# H2_Sensor.net
KiCad netlist of a schematic drawn in Altium Designer
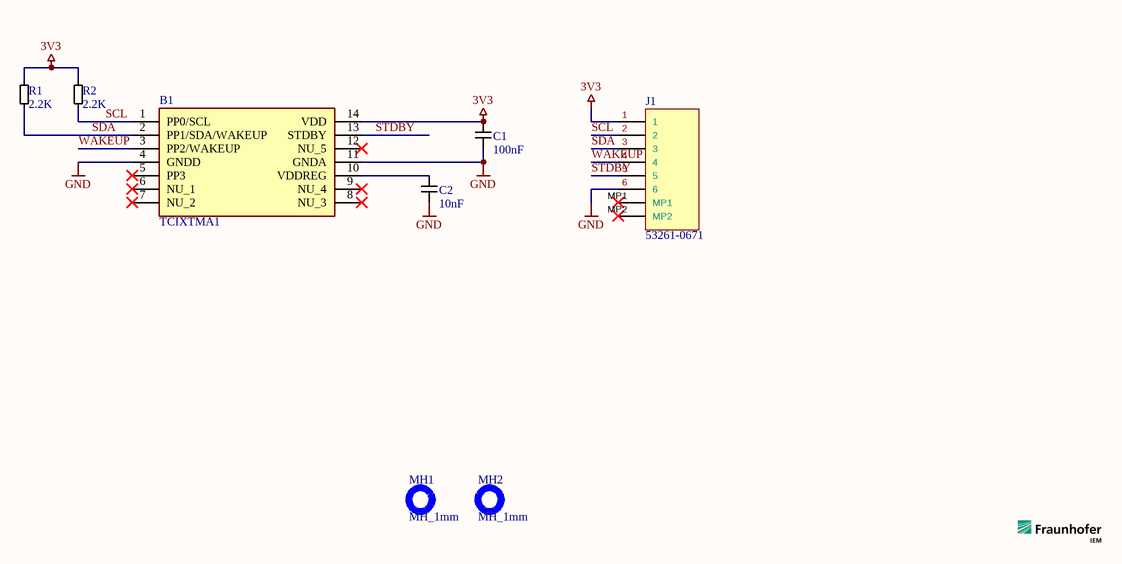
[diagram p0: H2 Sensor.SchDoc]

(export (version "E")
  (design (tool "Eeschema 10.0.6"))
  (components
    (comp (ref "B1")
      (value "TCIXTMA1")
      (footprint "SOP65P890X370-14N")
      (libsource (lib "Schlib1_Farhan") (part "TCIXTMA1"))
    )
    (comp (ref "C1")
      (value "100nF")
      (footprint "Capacitor 0402_1005Metric SMD")
      (description "Capacitor 0402_1005Metric SMD")
      (libsource (lib "Schlib1_Farhan") (part "Capacitor 0402_1005Metric SMD"))
    )
    (comp (ref "C2")
      (value "10nF")
      (footprint "Capacitor 0402_1005Metric SMD")
      (description "Capacitor 0402_1005Metric SMD")
      (libsource (lib "Schlib1_Farhan") (part "Capacitor 0402_1005Metric SMD"))
    )
    (comp (ref "J1")
      (value "53261-0671")
      (footprint "53261-0671")
      (description "PicoBlade 1x6 Horizontal \r\nPCB Header 1.25mm Pitch")
      (libsource (lib "Schlib1_Farhan") (part "53261-0671"))
    )
    (comp (ref "MH1")
      (value "MH_1mm")
      (footprint "MountingHole_1mm_M1")
      (libsource (lib "Schlib1_Farhan") (part "MountingHole_1mm_M1"))
    )
    (comp (ref "MH2")
      (value "MH_1mm")
      (footprint "MountingHole_1mm_M1")
      (libsource (lib "Schlib1_Farhan") (part "MountingHole_1mm_M1"))
    )
    (comp (ref "R1")
      (value "2.2K")
      (footprint "Resistor 0402_1005Metric SMD")
      (description "Resistor 0402_1005Metric SMD")
      (libsource (lib "Schlib1_Farhan") (part "Resistor 0402_1005Metric SMD"))
    )
    (comp (ref "R2")
      (value "2.2K")
      (footprint "Resistor 0402_1005Metric SMD")
      (description "Resistor 0402_1005Metric SMD")
      (libsource (lib "Schlib1_Farhan") (part "Resistor 0402_1005Metric SMD"))
    )
  )
  (nets
    (net (code "1") (name "/SCL") (class "Default")
      (node (ref "B1") (pin "1") (pinfunction "PP0/SCL_1") (pintype "passive"))
      (node (ref "J1") (pin "2") (pinfunction "2_2") (pintype "passive"))
      (node (ref "R2") (pin "1") (pinfunction "1_1") (pintype "passive"))
    )
    (net (code "2") (name "/SDA") (class "Default")
      (node (ref "B1") (pin "2") (pinfunction "PP1/SDA/WAKEUP_2") (pintype "passive"))
      (node (ref "J1") (pin "3") (pinfunction "3_3") (pintype "passive"))
      (node (ref "R1") (pin "1") (pinfunction "1_1") (pintype "passive"))
    )
    (net (code "3") (name "/STDBY") (class "Default")
      (node (ref "B1") (pin "13") (pinfunction "STDBY_13") (pintype "passive"))
      (node (ref "J1") (pin "5") (pinfunction "5_5") (pintype "passive"))
    )
    (net (code "4") (name "/WAKEUP") (class "Default")
      (node (ref "B1") (pin "3") (pinfunction "PP2/WAKEUP_3") (pintype "passive"))
      (node (ref "J1") (pin "4") (pinfunction "4_4") (pintype "passive"))
    )
    (net (code "5") (name "3V3") (class "Default")
      (node (ref "B1") (pin "14") (pinfunction "VDD_14") (pintype "passive"))
      (node (ref "C1") (pin "1") (pinfunction "1_1") (pintype "passive"))
      (node (ref "J1") (pin "1") (pinfunction "1_1") (pintype "passive"))
      (node (ref "R1") (pin "2") (pinfunction "2_2") (pintype "passive"))
      (node (ref "R2") (pin "2") (pinfunction "2_2") (pintype "passive"))
    )
    (net (code "6") (name "GND") (class "Default")
      (node (ref "B1") (pin "11") (pinfunction "GNDA_11") (pintype "passive"))
      (node (ref "B1") (pin "4") (pinfunction "GNDD_4") (pintype "passive"))
      (node (ref "C1") (pin "2") (pinfunction "2_2") (pintype "passive"))
      (node (ref "C2") (pin "2") (pinfunction "2_2") (pintype "passive"))
      (node (ref "J1") (pin "6") (pinfunction "6_6") (pintype "passive"))
    )
    (net (code "7") (name "Net-(B1-VDDREG)") (class "Default")
      (node (ref "B1") (pin "10") (pinfunction "VDDREG_10") (pintype "passive"))
      (node (ref "C2") (pin "1") (pinfunction "1_1") (pintype "passive"))
    )
    (net (code "8") (name "unconnected-(B1-NU_1-Pad6)") (class "Default")
      (node (ref "B1") (pin "6") (pinfunction "NU_1_6") (pintype "passive+no_connect"))
    )
    (net (code "9") (name "unconnected-(B1-NU_2-Pad7)") (class "Default")
      (node (ref "B1") (pin "7") (pinfunction "NU_2_7") (pintype "passive+no_connect"))
    )
    (net (code "10") (name "unconnected-(B1-NU_3-Pad8)") (class "Default")
      (node (ref "B1") (pin "8") (pinfunction "NU_3_8") (pintype "passive+no_connect"))
    )
    (net (code "11") (name "unconnected-(B1-NU_4-Pad9)") (class "Default")
      (node (ref "B1") (pin "9") (pinfunction "NU_4_9") (pintype "passive+no_connect"))
    )
    (net (code "12") (name "unconnected-(B1-NU_5-Pad12)") (class "Default")
      (node (ref "B1") (pin "12") (pinfunction "NU_5_12") (pintype "passive+no_connect"))
    )
    (net (code "13") (name "unconnected-(B1-PP3-Pad5)") (class "Default")
      (node (ref "B1") (pin "5") (pinfunction "PP3_5") (pintype "passive+no_connect"))
    )
    (net (code "14") (name "unconnected-(J1-PadMP1)") (class "Default")
      (node (ref "J1") (pin "MP1") (pinfunction "MP1_MP1") (pintype "passive+no_connect"))
    )
    (net (code "15") (name "unconnected-(J1-PadMP2)") (class "Default")
      (node (ref "J1") (pin "MP2") (pinfunction "MP2_MP2") (pintype "passive+no_connect"))
    )
  )
)
